# led-board.net
KiCad netlist of a schematic drawn in EAGLE
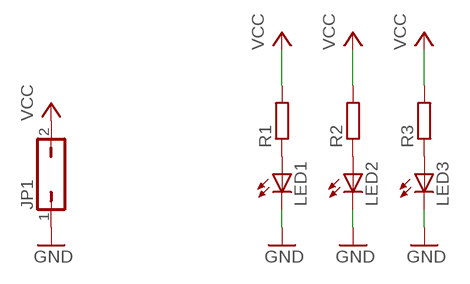
[diagram p0: schematic, sheet 1]

(export (version "E")
  (design (tool "Eeschema 10.0.6"))
  (components
    (comp (ref "JP1")
      (value "JP1Q")
      (footprint "eagle-import:JP1")
      (libsource (lib "eagle-import") (part "JP1Q"))
    )
    (comp (ref "LED1")
      (value "LED5MM")
      (footprint "eagle-import:LED5MM")
      (libsource (lib "eagle-import") (part "LED5MM"))
    )
    (comp (ref "LED2")
      (value "LED5MM")
      (footprint "eagle-import:LED5MM")
      (libsource (lib "eagle-import") (part "LED5MM"))
    )
    (comp (ref "LED3")
      (value "LED5MM")
      (footprint "eagle-import:LED5MM")
      (libsource (lib "eagle-import") (part "LED5MM"))
    )
    (comp (ref "R1")
      (value "R-EU_0414/15")
      (footprint "eagle-import:0414_15")
      (libsource (lib "eagle-import") (part "R-EU_0414/15"))
    )
    (comp (ref "R2")
      (value "R-EU_0414/15")
      (footprint "eagle-import:0414_15")
      (libsource (lib "eagle-import") (part "R-EU_0414/15"))
    )
    (comp (ref "R3")
      (value "R-EU_0414/15")
      (footprint "eagle-import:0414_15")
      (libsource (lib "eagle-import") (part "R-EU_0414/15"))
    )
  )
  (nets
    (net (code "1") (name "GND") (class "Default")
      (node (ref "JP1") (pin "1") (pinfunction "1_1") (pintype "passive"))
      (node (ref "LED1") (pin "K") (pinfunction "C_K") (pintype "passive"))
      (node (ref "LED2") (pin "K") (pinfunction "C_K") (pintype "passive"))
      (node (ref "LED3") (pin "K") (pinfunction "C_K") (pintype "passive"))
    )
    (net (code "2") (name "Net-(LED1-PadA)") (class "Default")
      (node (ref "LED1") (pin "A") (pinfunction "A_A") (pintype "passive"))
      (node (ref "R1") (pin "1") (pinfunction "1_1") (pintype "passive"))
    )
    (net (code "3") (name "Net-(LED2-PadA)") (class "Default")
      (node (ref "LED2") (pin "A") (pinfunction "A_A") (pintype "passive"))
      (node (ref "R2") (pin "1") (pinfunction "1_1") (pintype "passive"))
    )
    (net (code "4") (name "Net-(LED3-PadA)") (class "Default")
      (node (ref "LED3") (pin "A") (pinfunction "A_A") (pintype "passive"))
      (node (ref "R3") (pin "1") (pinfunction "1_1") (pintype "passive"))
    )
    (net (code "5") (name "VCC") (class "Default")
      (node (ref "JP1") (pin "2") (pinfunction "2_2") (pintype "passive"))
      (node (ref "R1") (pin "2") (pinfunction "2_2") (pintype "passive"))
      (node (ref "R2") (pin "2") (pinfunction "2_2") (pintype "passive"))
      (node (ref "R3") (pin "2") (pinfunction "2_2") (pintype "passive"))
    )
  )
)
